# Applied-Procrastination-Fetch-Driver-Cir.net
KiCad netlist of a schematic drawn in EAGLE
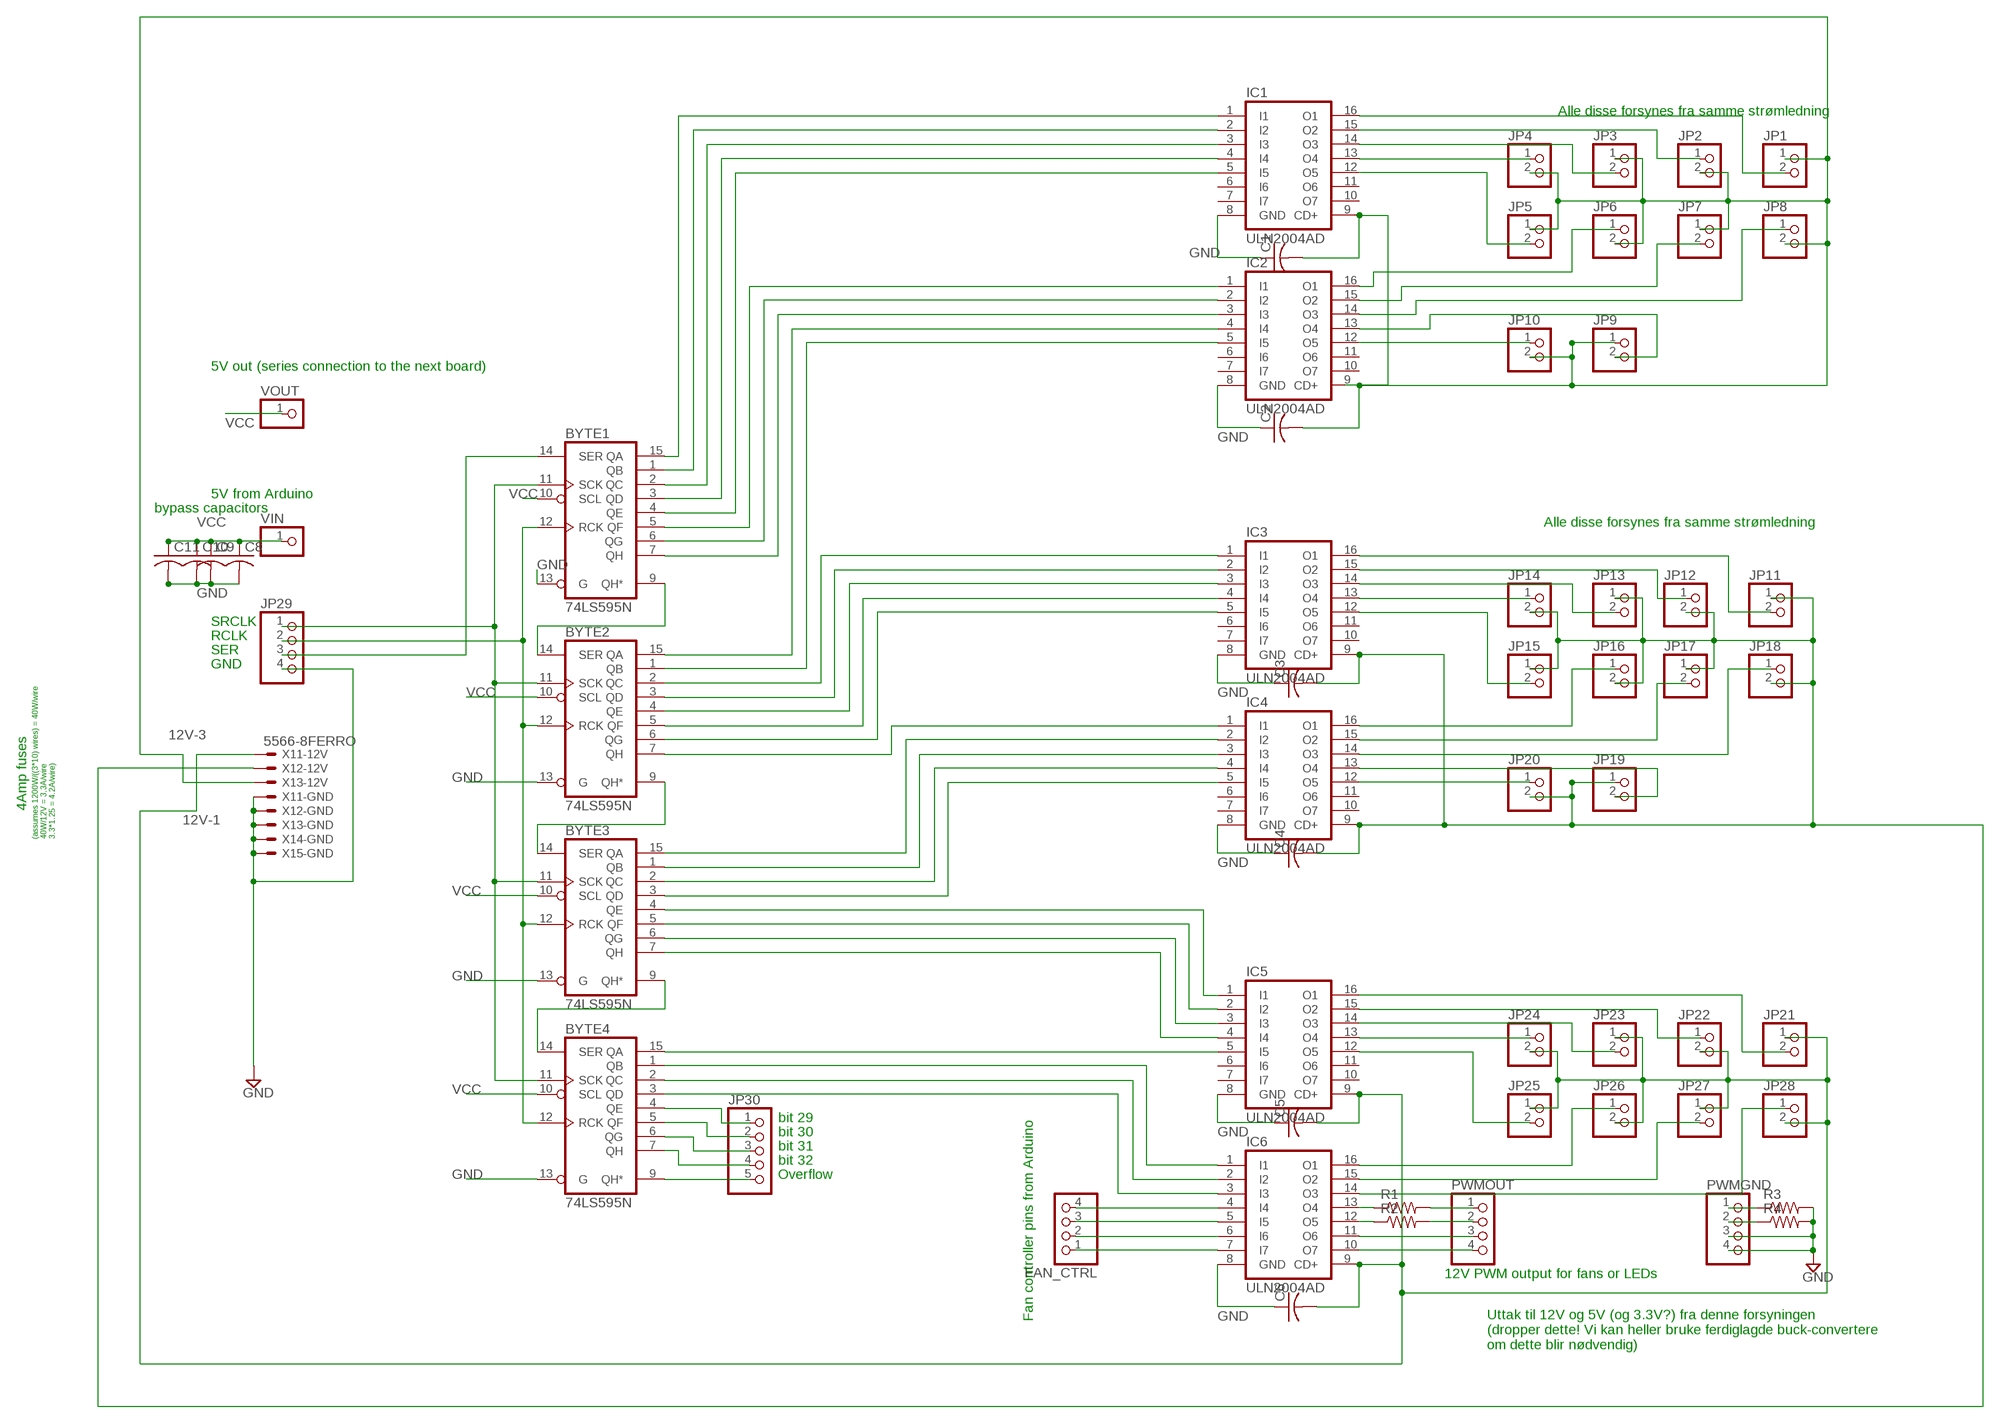
[diagram p0: schematic, sheet 1]

(export (version "E")
  (design (tool "Eeschema 10.0.6"))
  (components
    (comp (ref "BYTE1")
      (value "74LS595N")
      (footprint "eagle-import:DIL16")
      (libsource (lib "eagle-import") (part "74595NLS"))
    )
    (comp (ref "BYTE2")
      (value "74LS595N")
      (footprint "eagle-import:DIL16")
      (libsource (lib "eagle-import") (part "74595NLS"))
    )
    (comp (ref "BYTE3")
      (value "74LS595N")
      (footprint "eagle-import:DIL16")
      (libsource (lib "eagle-import") (part "74595NLS"))
    )
    (comp (ref "BYTE4")
      (value "74LS595N")
      (footprint "eagle-import:DIL16")
      (libsource (lib "eagle-import") (part "74595NLS"))
    )
    (comp (ref "C1")
      (value "C-USC0603")
      (footprint "eagle-import:C0603")
      (libsource (lib "eagle-import") (part "C-USC0603"))
    )
    (comp (ref "C2")
      (value "C-USC0603")
      (footprint "eagle-import:C0603")
      (libsource (lib "eagle-import") (part "C-USC0603"))
    )
    (comp (ref "C3")
      (value "C-USC0603")
      (footprint "eagle-import:C0603")
      (libsource (lib "eagle-import") (part "C-USC0603"))
    )
    (comp (ref "C4")
      (value "C-USC0603")
      (footprint "eagle-import:C0603")
      (libsource (lib "eagle-import") (part "C-USC0603"))
    )
    (comp (ref "C5")
      (value "C-USC0603")
      (footprint "eagle-import:C0603")
      (libsource (lib "eagle-import") (part "C-USC0603"))
    )
    (comp (ref "C6")
      (value "C-USC0603")
      (footprint "eagle-import:C0603")
      (libsource (lib "eagle-import") (part "C-USC0603"))
    )
    (comp (ref "C8")
      (value "C-USC0603")
      (footprint "eagle-import:C0603")
      (libsource (lib "eagle-import") (part "C-USC0603"))
    )
    (comp (ref "C9")
      (value "C-USC0603")
      (footprint "eagle-import:C0603")
      (libsource (lib "eagle-import") (part "C-USC0603"))
    )
    (comp (ref "C10")
      (value "C-USC0603")
      (footprint "eagle-import:C0603")
      (libsource (lib "eagle-import") (part "C-USC0603"))
    )
    (comp (ref "C11")
      (value "C-USC0603")
      (footprint "eagle-import:C0603")
      (libsource (lib "eagle-import") (part "C-USC0603"))
    )
    (comp (ref "FAN_CTRL")
      (value "PINHD-1X4")
      (footprint "eagle-import:1X04")
      (libsource (lib "eagle-import") (part "PINHD-1X4"))
    )
    (comp (ref "IC1")
      (value "ULN2004AD")
      (footprint "eagle-import:SO16")
      (libsource (lib "eagle-import") (part "ULN2004AD"))
    )
    (comp (ref "IC2")
      (value "ULN2004AD")
      (footprint "eagle-import:SO16")
      (libsource (lib "eagle-import") (part "ULN2004AD"))
    )
    (comp (ref "IC3")
      (value "ULN2004AD")
      (footprint "eagle-import:SO16")
      (libsource (lib "eagle-import") (part "ULN2004AD"))
    )
    (comp (ref "IC4")
      (value "ULN2004AD")
      (footprint "eagle-import:SO16")
      (libsource (lib "eagle-import") (part "ULN2004AD"))
    )
    (comp (ref "IC5")
      (value "ULN2004AD")
      (footprint "eagle-import:SO16")
      (libsource (lib "eagle-import") (part "ULN2004AD"))
    )
    (comp (ref "IC6")
      (value "ULN2004AD")
      (footprint "eagle-import:SO16")
      (libsource (lib "eagle-import") (part "ULN2004AD"))
    )
    (comp (ref "JP1")
      (value "PINHD-1X2SOLENOID-R")
      (footprint "eagle-import:SOLENOID-CONTACT-REVERSE")
      (libsource (lib "eagle-import") (part "PINHD-1X2SOLENOID-R"))
    )
    (comp (ref "JP2")
      (value "PINHD-1X2SOLENOID")
      (footprint "eagle-import:SOLENOID-CONTACT")
      (libsource (lib "eagle-import") (part "PINHD-1X2SOLENOID"))
    )
    (comp (ref "JP3")
      (value "PINHD-1X2SOLENOID-R")
      (footprint "eagle-import:SOLENOID-CONTACT-REVERSE")
      (libsource (lib "eagle-import") (part "PINHD-1X2SOLENOID-R"))
    )
    (comp (ref "JP4")
      (value "PINHD-1X2SOLENOID")
      (footprint "eagle-import:SOLENOID-CONTACT")
      (libsource (lib "eagle-import") (part "PINHD-1X2SOLENOID"))
    )
    (comp (ref "JP5")
      (value "PINHD-1X2SOLENOID-R")
      (footprint "eagle-import:SOLENOID-CONTACT-REVERSE")
      (libsource (lib "eagle-import") (part "PINHD-1X2SOLENOID-R"))
    )
    (comp (ref "JP6")
      (value "PINHD-1X2SOLENOID")
      (footprint "eagle-import:SOLENOID-CONTACT")
      (libsource (lib "eagle-import") (part "PINHD-1X2SOLENOID"))
    )
    (comp (ref "JP7")
      (value "PINHD-1X2SOLENOID-R")
      (footprint "eagle-import:SOLENOID-CONTACT-REVERSE")
      (libsource (lib "eagle-import") (part "PINHD-1X2SOLENOID-R"))
    )
    (comp (ref "JP8")
      (value "PINHD-1X2SOLENOID")
      (footprint "eagle-import:SOLENOID-CONTACT")
      (libsource (lib "eagle-import") (part "PINHD-1X2SOLENOID"))
    )
    (comp (ref "JP9")
      (value "PINHD-1X2SOLENOID-R")
      (footprint "eagle-import:SOLENOID-CONTACT-REVERSE")
      (libsource (lib "eagle-import") (part "PINHD-1X2SOLENOID-R"))
    )
    (comp (ref "JP10")
      (value "PINHD-1X2SOLENOID")
      (footprint "eagle-import:SOLENOID-CONTACT")
      (libsource (lib "eagle-import") (part "PINHD-1X2SOLENOID"))
    )
    (comp (ref "JP11")
      (value "PINHD-1X2SOLENOID-R")
      (footprint "eagle-import:SOLENOID-CONTACT-REVERSE")
      (libsource (lib "eagle-import") (part "PINHD-1X2SOLENOID-R"))
    )
    (comp (ref "JP12")
      (value "PINHD-1X2SOLENOID")
      (footprint "eagle-import:SOLENOID-CONTACT")
      (libsource (lib "eagle-import") (part "PINHD-1X2SOLENOID"))
    )
    (comp (ref "JP13")
      (value "PINHD-1X2SOLENOID-R")
      (footprint "eagle-import:SOLENOID-CONTACT-REVERSE")
      (libsource (lib "eagle-import") (part "PINHD-1X2SOLENOID-R"))
    )
    (comp (ref "JP14")
      (value "PINHD-1X2SOLENOID")
      (footprint "eagle-import:SOLENOID-CONTACT")
      (libsource (lib "eagle-import") (part "PINHD-1X2SOLENOID"))
    )
    (comp (ref "JP15")
      (value "PINHD-1X2SOLENOID-R")
      (footprint "eagle-import:SOLENOID-CONTACT-REVERSE")
      (libsource (lib "eagle-import") (part "PINHD-1X2SOLENOID-R"))
    )
    (comp (ref "JP16")
      (value "PINHD-1X2SOLENOID")
      (footprint "eagle-import:SOLENOID-CONTACT")
      (libsource (lib "eagle-import") (part "PINHD-1X2SOLENOID"))
    )
    (comp (ref "JP17")
      (value "PINHD-1X2SOLENOID-R")
      (footprint "eagle-import:SOLENOID-CONTACT-REVERSE")
      (libsource (lib "eagle-import") (part "PINHD-1X2SOLENOID-R"))
    )
    (comp (ref "JP18")
      (value "PINHD-1X2SOLENOID")
      (footprint "eagle-import:SOLENOID-CONTACT")
      (libsource (lib "eagle-import") (part "PINHD-1X2SOLENOID"))
    )
    (comp (ref "JP19")
      (value "PINHD-1X2SOLENOID-R")
      (footprint "eagle-import:SOLENOID-CONTACT-REVERSE")
      (libsource (lib "eagle-import") (part "PINHD-1X2SOLENOID-R"))
    )
    (comp (ref "JP20")
      (value "PINHD-1X2SOLENOID")
      (footprint "eagle-import:SOLENOID-CONTACT")
      (libsource (lib "eagle-import") (part "PINHD-1X2SOLENOID"))
    )
    (comp (ref "JP21")
      (value "PINHD-1X2SOLENOID-R")
      (footprint "eagle-import:SOLENOID-CONTACT-REVERSE")
      (libsource (lib "eagle-import") (part "PINHD-1X2SOLENOID-R"))
    )
    (comp (ref "JP22")
      (value "PINHD-1X2SOLENOID")
      (footprint "eagle-import:SOLENOID-CONTACT")
      (libsource (lib "eagle-import") (part "PINHD-1X2SOLENOID"))
    )
    (comp (ref "JP23")
      (value "PINHD-1X2SOLENOID-R")
      (footprint "eagle-import:SOLENOID-CONTACT-REVERSE")
      (libsource (lib "eagle-import") (part "PINHD-1X2SOLENOID-R"))
    )
    (comp (ref "JP24")
      (value "PINHD-1X2SOLENOID")
      (footprint "eagle-import:SOLENOID-CONTACT")
      (libsource (lib "eagle-import") (part "PINHD-1X2SOLENOID"))
    )
    (comp (ref "JP25")
      (value "PINHD-1X2SOLENOID-R")
      (footprint "eagle-import:SOLENOID-CONTACT-REVERSE")
      (libsource (lib "eagle-import") (part "PINHD-1X2SOLENOID-R"))
    )
    (comp (ref "JP26")
      (value "PINHD-1X2SOLENOID")
      (footprint "eagle-import:SOLENOID-CONTACT")
      (libsource (lib "eagle-import") (part "PINHD-1X2SOLENOID"))
    )
    (comp (ref "JP27")
      (value "PINHD-1X2SOLENOID-R")
      (footprint "eagle-import:SOLENOID-CONTACT-REVERSE")
      (libsource (lib "eagle-import") (part "PINHD-1X2SOLENOID-R"))
    )
    (comp (ref "JP28")
      (value "PINHD-1X2SOLENOID")
      (footprint "eagle-import:SOLENOID-CONTACT")
      (libsource (lib "eagle-import") (part "PINHD-1X2SOLENOID"))
    )
    (comp (ref "JP29")
      (value "PINHD-1X4")
      (footprint "eagle-import:1X04")
      (libsource (lib "eagle-import") (part "PINHD-1X4"))
    )
    (comp (ref "JP30")
      (value "PINHD-1X5")
      (footprint "eagle-import:1X05")
      (libsource (lib "eagle-import") (part "PINHD-1X5"))
    )
    (comp (ref "PWMGND")
      (value "PINHD-1X4")
      (footprint "eagle-import:1X04")
      (libsource (lib "eagle-import") (part "PINHD-1X4"))
    )
    (comp (ref "PWMOUT")
      (value "PINHD-1X4")
      (footprint "eagle-import:1X04")
      (libsource (lib "eagle-import") (part "PINHD-1X4"))
    )
    (comp (ref "R1")
      (value "R-US_R0603")
      (footprint "eagle-import:R0603")
      (libsource (lib "eagle-import") (part "R-US_R0603"))
    )
    (comp (ref "R2")
      (value "R-US_R0603")
      (footprint "eagle-import:R0603")
      (libsource (lib "eagle-import") (part "R-US_R0603"))
    )
    (comp (ref "R3")
      (value "R-US_R0603")
      (footprint "eagle-import:R0603")
      (libsource (lib "eagle-import") (part "R-US_R0603"))
    )
    (comp (ref "R4")
      (value "R-US_R0603")
      (footprint "eagle-import:R0603")
      (libsource (lib "eagle-import") (part "R-US_R0603"))
    )
    (comp (ref "VIN")
      (value "PINHD-1X1")
      (footprint "eagle-import:1X01")
      (libsource (lib "eagle-import") (part "PINHD-1X1"))
    )
    (comp (ref "VOUT")
      (value "PINHD-1X1")
      (footprint "eagle-import:1X01")
      (libsource (lib "eagle-import") (part "PINHD-1X1"))
    )
    (comp (ref "X1")
      (value "5566-8FERRO")
      (footprint "eagle-import:5566-8-CLEAN")
      (libsource (lib "eagle-import") (part "5566-8FERRO"))
    )
  )
  (nets
    (net (code "1") (name "/12V-1") (class "Default")
      (node (ref "C5") (pin "2") (pinfunction "2_2") (pintype "passive"))
      (node (ref "C6") (pin "2") (pinfunction "2_2") (pintype "passive"))
      (node (ref "IC5") (pin "9") (pinfunction "CD+_9") (pintype "passive"))
      (node (ref "IC6") (pin "9") (pinfunction "CD+_9") (pintype "passive"))
      (node (ref "JP21") (pin "1") (pinfunction "1_1") (pintype "passive"))
      (node (ref "JP22") (pin "2") (pinfunction "2_2") (pintype "passive"))
      (node (ref "JP23") (pin "1") (pinfunction "1_1") (pintype "passive"))
      (node (ref "JP24") (pin "2") (pinfunction "2_2") (pintype "passive"))
      (node (ref "JP25") (pin "1") (pinfunction "1_1") (pintype "passive"))
      (node (ref "JP26") (pin "2") (pinfunction "2_2") (pintype "passive"))
      (node (ref "JP27") (pin "1") (pinfunction "1_1") (pintype "passive"))
      (node (ref "JP28") (pin "2") (pinfunction "2_2") (pintype "passive"))
      (node (ref "X1") (pin "1") (pinfunction "S_1") (pintype "passive"))
    )
    (net (code "2") (name "/12V-3") (class "Default")
      (node (ref "C1") (pin "2") (pinfunction "2_2") (pintype "passive"))
      (node (ref "C2") (pin "2") (pinfunction "2_2") (pintype "passive"))
      (node (ref "IC1") (pin "9") (pinfunction "CD+_9") (pintype "passive"))
      (node (ref "IC2") (pin "9") (pinfunction "CD+_9") (pintype "passive"))
      (node (ref "JP1") (pin "1") (pinfunction "1_1") (pintype "passive"))
      (node (ref "JP10") (pin "2") (pinfunction "2_2") (pintype "passive"))
      (node (ref "JP2") (pin "2") (pinfunction "2_2") (pintype "passive"))
      (node (ref "JP3") (pin "1") (pinfunction "1_1") (pintype "passive"))
      (node (ref "JP4") (pin "2") (pinfunction "2_2") (pintype "passive"))
      (node (ref "JP5") (pin "1") (pinfunction "1_1") (pintype "passive"))
      (node (ref "JP6") (pin "2") (pinfunction "2_2") (pintype "passive"))
      (node (ref "JP7") (pin "1") (pinfunction "1_1") (pintype "passive"))
      (node (ref "JP8") (pin "2") (pinfunction "2_2") (pintype "passive"))
      (node (ref "JP9") (pin "1") (pinfunction "1_1") (pintype "passive"))
      (node (ref "X1") (pin "3") (pinfunction "S_3") (pintype "passive"))
    )
    (net (code "3") (name "/VCC") (class "Default")
      (node (ref "BYTE1") (pin "10") (pinfunction "SCL_10") (pintype "input"))
      (node (ref "BYTE2") (pin "10") (pinfunction "SCL_10") (pintype "input"))
      (node (ref "BYTE3") (pin "10") (pinfunction "SCL_10") (pintype "input"))
      (node (ref "BYTE4") (pin "10") (pinfunction "SCL_10") (pintype "input"))
      (node (ref "C10") (pin "1") (pinfunction "1_1") (pintype "passive"))
      (node (ref "C11") (pin "1") (pinfunction "1_1") (pintype "passive"))
      (node (ref "C8") (pin "1") (pinfunction "1_1") (pintype "passive"))
      (node (ref "C9") (pin "1") (pinfunction "1_1") (pintype "passive"))
      (node (ref "VIN") (pin "1") (pinfunction "1_1") (pintype "passive"))
      (node (ref "VOUT") (pin "1") (pinfunction "1_1") (pintype "passive"))
    )
    (net (code "4") (name "GND") (class "Default")
      (node (ref "BYTE1") (pin "13") (pinfunction "G_13") (pintype "input"))
      (node (ref "BYTE2") (pin "13") (pinfunction "G_13") (pintype "input"))
      (node (ref "BYTE3") (pin "13") (pinfunction "G_13") (pintype "input"))
      (node (ref "BYTE4") (pin "13") (pinfunction "G_13") (pintype "input"))
      (node (ref "C1") (pin "1") (pinfunction "1_1") (pintype "passive"))
      (node (ref "C10") (pin "2") (pinfunction "2_2") (pintype "passive"))
      (node (ref "C11") (pin "2") (pinfunction "2_2") (pintype "passive"))
      (node (ref "C2") (pin "1") (pinfunction "1_1") (pintype "passive"))
      (node (ref "C3") (pin "1") (pinfunction "1_1") (pintype "passive"))
      (node (ref "C4") (pin "1") (pinfunction "1_1") (pintype "passive"))
      (node (ref "C5") (pin "1") (pinfunction "1_1") (pintype "passive"))
      (node (ref "C6") (pin "1") (pinfunction "1_1") (pintype "passive"))
      (node (ref "C8") (pin "2") (pinfunction "2_2") (pintype "passive"))
      (node (ref "C9") (pin "2") (pinfunction "2_2") (pintype "passive"))
      (node (ref "IC1") (pin "8") (pinfunction "GND_8") (pintype "power_in"))
      (node (ref "IC2") (pin "8") (pinfunction "GND_8") (pintype "power_in"))
      (node (ref "IC3") (pin "8") (pinfunction "GND_8") (pintype "power_in"))
      (node (ref "IC4") (pin "8") (pinfunction "GND_8") (pintype "power_in"))
      (node (ref "IC5") (pin "8") (pinfunction "GND_8") (pintype "power_in"))
      (node (ref "IC6") (pin "8") (pinfunction "GND_8") (pintype "power_in"))
      (node (ref "JP29") (pin "4") (pinfunction "4_4") (pintype "passive"))
      (node (ref "PWMGND") (pin "3") (pinfunction "3_3") (pintype "passive"))
      (node (ref "PWMGND") (pin "4") (pinfunction "4_4") (pintype "passive"))
      (node (ref "R3") (pin "2") (pinfunction "2_2") (pintype "passive"))
      (node (ref "R4") (pin "2") (pinfunction "2_2") (pintype "passive"))
      (node (ref "X1") (pin "4") (pinfunction "S_4") (pintype "passive"))
      (node (ref "X1") (pin "5") (pinfunction "S_5") (pintype "passive"))
      (node (ref "X1") (pin "6") (pinfunction "S_6") (pintype "passive"))
      (node (ref "X1") (pin "7") (pinfunction "S_7") (pintype "passive"))
      (node (ref "X1") (pin "8") (pinfunction "S_8") (pintype "passive"))
    )
    (net (code "5") (name "Net-(BYTE1A-QA)") (class "Default")
      (node (ref "BYTE1") (pin "15") (pinfunction "QA_15") (pintype "tri_state"))
      (node (ref "IC1") (pin "1") (pinfunction "I1_1") (pintype "input"))
    )
    (net (code "6") (name "Net-(BYTE1A-QB)") (class "Default")
      (node (ref "BYTE1") (pin "1") (pinfunction "QB_1") (pintype "tri_state"))
      (node (ref "IC1") (pin "2") (pinfunction "I2_2") (pintype "input"))
    )
    (net (code "7") (name "Net-(BYTE1A-QC)") (class "Default")
      (node (ref "BYTE1") (pin "2") (pinfunction "QC_2") (pintype "tri_state"))
      (node (ref "IC1") (pin "3") (pinfunction "I3_3") (pintype "input"))
    )
    (net (code "8") (name "Net-(BYTE1A-QD)") (class "Default")
      (node (ref "BYTE1") (pin "3") (pinfunction "QD_3") (pintype "tri_state"))
      (node (ref "IC1") (pin "4") (pinfunction "I4_4") (pintype "input"))
    )
    (net (code "9") (name "Net-(BYTE1A-QE)") (class "Default")
      (node (ref "BYTE1") (pin "4") (pinfunction "QE_4") (pintype "tri_state"))
      (node (ref "IC1") (pin "5") (pinfunction "I5_5") (pintype "input"))
    )
    (net (code "10") (name "Net-(BYTE1A-QF)") (class "Default")
      (node (ref "BYTE1") (pin "5") (pinfunction "QF_5") (pintype "tri_state"))
      (node (ref "IC2") (pin "1") (pinfunction "I1_1") (pintype "input"))
    )
    (net (code "11") (name "Net-(BYTE1A-QG)") (class "Default")
      (node (ref "BYTE1") (pin "6") (pinfunction "QG_6") (pintype "tri_state"))
      (node (ref "IC2") (pin "2") (pinfunction "I2_2") (pintype "input"))
    )
    (net (code "12") (name "Net-(BYTE1A-QH)") (class "Default")
      (node (ref "BYTE1") (pin "7") (pinfunction "QH_7") (pintype "tri_state"))
      (node (ref "IC2") (pin "3") (pinfunction "I3_3") (pintype "input"))
    )
    (net (code "13") (name "Net-(BYTE1A-QH*)") (class "Default")
      (node (ref "BYTE1") (pin "9") (pinfunction "QH*_9") (pintype "tri_state"))
      (node (ref "BYTE2") (pin "14") (pinfunction "SER_14") (pintype "input"))
    )
    (net (code "14") (name "Net-(BYTE1A-RCK)") (class "Default")
      (node (ref "BYTE1") (pin "12") (pinfunction "RCK_12") (pintype "input"))
      (node (ref "BYTE2") (pin "12") (pinfunction "RCK_12") (pintype "input"))
      (node (ref "BYTE3") (pin "12") (pinfunction "RCK_12") (pintype "input"))
      (node (ref "BYTE4") (pin "12") (pinfunction "RCK_12") (pintype "input"))
      (node (ref "JP29") (pin "2") (pinfunction "2_2") (pintype "passive"))
    )
    (net (code "15") (name "Net-(BYTE1A-SCK)") (class "Default")
      (node (ref "BYTE1") (pin "11") (pinfunction "SCK_11") (pintype "input"))
      (node (ref "BYTE2") (pin "11") (pinfunction "SCK_11") (pintype "input"))
      (node (ref "BYTE3") (pin "11") (pinfunction "SCK_11") (pintype "input"))
      (node (ref "BYTE4") (pin "11") (pinfunction "SCK_11") (pintype "input"))
      (node (ref "JP29") (pin "1") (pinfunction "1_1") (pintype "passive"))
    )
    (net (code "16") (name "Net-(BYTE1A-SER)") (class "Default")
      (node (ref "BYTE1") (pin "14") (pinfunction "SER_14") (pintype "input"))
      (node (ref "JP29") (pin "3") (pinfunction "3_3") (pintype "passive"))
    )
    (net (code "17") (name "Net-(BYTE2A-QA)") (class "Default")
      (node (ref "BYTE2") (pin "15") (pinfunction "QA_15") (pintype "tri_state"))
      (node (ref "IC2") (pin "4") (pinfunction "I4_4") (pintype "input"))
    )
    (net (code "18") (name "Net-(BYTE2A-QB)") (class "Default")
      (node (ref "BYTE2") (pin "1") (pinfunction "QB_1") (pintype "tri_state"))
      (node (ref "IC2") (pin "5") (pinfunction "I5_5") (pintype "input"))
    )
    (net (code "19") (name "Net-(BYTE2A-QC)") (class "Default")
      (node (ref "BYTE2") (pin "2") (pinfunction "QC_2") (pintype "tri_state"))
      (node (ref "IC3") (pin "1") (pinfunction "I1_1") (pintype "input"))
    )
    (net (code "20") (name "Net-(BYTE2A-QD)") (class "Default")
      (node (ref "BYTE2") (pin "3") (pinfunction "QD_3") (pintype "tri_state"))
      (node (ref "IC3") (pin "2") (pinfunction "I2_2") (pintype "input"))
    )
    (net (code "21") (name "Net-(BYTE2A-QE)") (class "Default")
      (node (ref "BYTE2") (pin "4") (pinfunction "QE_4") (pintype "tri_state"))
      (node (ref "IC3") (pin "3") (pinfunction "I3_3") (pintype "input"))
    )
    (net (code "22") (name "Net-(BYTE2A-QF)") (class "Default")
      (node (ref "BYTE2") (pin "5") (pinfunction "QF_5") (pintype "tri_state"))
      (node (ref "IC3") (pin "4") (pinfunction "I4_4") (pintype "input"))
    )
    (net (code "23") (name "Net-(BYTE2A-QG)") (class "Default")
      (node (ref "BYTE2") (pin "6") (pinfunction "QG_6") (pintype "tri_state"))
      (node (ref "IC3") (pin "5") (pinfunction "I5_5") (pintype "input"))
    )
    (net (code "24") (name "Net-(BYTE2A-QH)") (class "Default")
      (node (ref "BYTE2") (pin "7") (pinfunction "QH_7") (pintype "tri_state"))
      (node (ref "IC4") (pin "1") (pinfunction "I1_1") (pintype "input"))
    )
    (net (code "25") (name "Net-(BYTE2A-QH*)") (class "Default")
      (node (ref "BYTE2") (pin "9") (pinfunction "QH*_9") (pintype "tri_state"))
      (node (ref "BYTE3") (pin "14") (pinfunction "SER_14") (pintype "input"))
    )
    (net (code "26") (name "Net-(BYTE3A-QA)") (class "Default")
      (node (ref "BYTE3") (pin "15") (pinfunction "QA_15") (pintype "tri_state"))
      (node (ref "IC4") (pin "2") (pinfunction "I2_2") (pintype "input"))
    )
    (net (code "27") (name "Net-(BYTE3A-QB)") (class "Default")
      (node (ref "BYTE3") (pin "1") (pinfunction "QB_1") (pintype "tri_state"))
      (node (ref "IC4") (pin "3") (pinfunction "I3_3") (pintype "input"))
    )
    (net (code "28") (name "Net-(BYTE3A-QC)") (class "Default")
      (node (ref "BYTE3") (pin "2") (pinfunction "QC_2") (pintype "tri_state"))
      (node (ref "IC4") (pin "4") (pinfunction "I4_4") (pintype "input"))
    )
    (net (code "29") (name "Net-(BYTE3A-QD)") (class "Default")
      (node (ref "BYTE3") (pin "3") (pinfunction "QD_3") (pintype "tri_state"))
      (node (ref "IC4") (pin "5") (pinfunction "I5_5") (pintype "input"))
    )
    (net (code "30") (name "Net-(BYTE3A-QE)") (class "Default")
      (node (ref "BYTE3") (pin "4") (pinfunction "QE_4") (pintype "tri_state"))
      (node (ref "IC5") (pin "1") (pinfunction "I1_1") (pintype "input"))
    )
    (net (code "31") (name "Net-(BYTE3A-QF)") (class "Default")
      (node (ref "BYTE3") (pin "5") (pinfunction "QF_5") (pintype "tri_state"))
      (node (ref "IC5") (pin "2") (pinfunction "I2_2") (pintype "input"))
    )
    (net (code "32") (name "Net-(BYTE3A-QG)") (class "Default")
      (node (ref "BYTE3") (pin "6") (pinfunction "QG_6") (pintype "tri_state"))
      (node (ref "IC5") (pin "3") (pinfunction "I3_3") (pintype "input"))
    )
    (net (code "33") (name "Net-(BYTE3A-QH)") (class "Default")
      (node (ref "BYTE3") (pin "7") (pinfunction "QH_7") (pintype "tri_state"))
      (node (ref "IC5") (pin "4") (pinfunction "I4_4") (pintype "input"))
    )
    (net (code "34") (name "Net-(BYTE3A-QH*)") (class "Default")
      (node (ref "BYTE3") (pin "9") (pinfunction "QH*_9") (pintype "tri_state"))
      (node (ref "BYTE4") (pin "14") (pinfunction "SER_14") (pintype "input"))
    )
    (net (code "35") (name "Net-(BYTE4A-QA)") (class "Default")
      (node (ref "BYTE4") (pin "15") (pinfunction "QA_15") (pintype "tri_state"))
      (node (ref "IC5") (pin "5") (pinfunction "I5_5") (pintype "input"))
    )
    (net (code "36") (name "Net-(BYTE4A-QB)") (class "Default")
      (node (ref "BYTE4") (pin "1") (pinfunction "QB_1") (pintype "tri_state"))
      (node (ref "IC6") (pin "1") (pinfunction "I1_1") (pintype "input"))
    )
    (net (code "37") (name "Net-(BYTE4A-QC)") (class "Default")
      (node (ref "BYTE4") (pin "2") (pinfunction "QC_2") (pintype "tri_state"))
      (node (ref "IC6") (pin "2") (pinfunction "I2_2") (pintype "input"))
    )
    (net (code "38") (name "Net-(BYTE4A-QD)") (class "Default")
      (node (ref "BYTE4") (pin "3") (pinfunction "QD_3") (pintype "tri_state"))
      (node (ref "IC6") (pin "3") (pinfunction "I3_3") (pintype "input"))
    )
    (net (code "39") (name "Net-(BYTE4A-QE)") (class "Default")
      (node (ref "BYTE4") (pin "4") (pinfunction "QE_4") (pintype "tri_state"))
      (node (ref "JP30") (pin "1") (pinfunction "1_1") (pintype "passive"))
    )
    (net (code "40") (name "Net-(BYTE4A-QF)") (class "Default")
      (node (ref "BYTE4") (pin "5") (pinfunction "QF_5") (pintype "tri_state"))
      (node (ref "JP30") (pin "2") (pinfunction "2_2") (pintype "passive"))
    )
    (net (code "41") (name "Net-(BYTE4A-QG)") (class "Default")
      (node (ref "BYTE4") (pin "6") (pinfunction "QG_6") (pintype "tri_state"))
      (node (ref "JP30") (pin "3") (pinfunction "3_3") (pintype "passive"))
    )
    (net (code "42") (name "Net-(BYTE4A-QH)") (class "Default")
      (node (ref "BYTE4") (pin "7") (pinfunction "QH_7") (pintype "tri_state"))
      (node (ref "JP30") (pin "4") (pinfunction "4_4") (pintype "passive"))
    )
    (net (code "43") (name "Net-(BYTE4A-QH*)") (class "Default")
      (node (ref "BYTE4") (pin "9") (pinfunction "QH*_9") (pintype "tri_state"))
      (node (ref "JP30") (pin "5") (pinfunction "5_5") (pintype "passive"))
    )
    (net (code "44") (name "Net-(IC1-O1)") (class "Default")
      (node (ref "IC1") (pin "16") (pinfunction "O1_16") (pintype "open_collector"))
      (node (ref "JP1") (pin "2") (pinfunction "2_2") (pintype "passive"))
    )
    (net (code "45") (name "Net-(IC1-O2)") (class "Default")
      (node (ref "IC1") (pin "15") (pinfunction "O2_15") (pintype "open_collector"))
      (node (ref "JP2") (pin "1") (pinfunction "1_1") (pintype "passive"))
    )
    (net (code "46") (name "Net-(IC1-O3)") (class "Default")
      (node (ref "IC1") (pin "14") (pinfunction "O3_14") (pintype "open_collector"))
      (node (ref "JP3") (pin "2") (pinfunction "2_2") (pintype "passive"))
    )
    (net (code "47") (name "Net-(IC1-O4)") (class "Default")
      (node (ref "IC1") (pin "13") (pinfunction "O4_13") (pintype "open_collector"))
      (node (ref "JP4") (pin "1") (pinfunction "1_1") (pintype "passive"))
    )
    (net (code "48") (name "Net-(IC1-O5)") (class "Default")
      (node (ref "IC1") (pin "12") (pinfunction "O5_12") (pintype "open_collector"))
      (node (ref "JP5") (pin "2") (pinfunction "2_2") (pintype "passive"))
    )
    (net (code "49") (name "Net-(IC2-O1)") (class "Default")
      (node (ref "IC2") (pin "16") (pinfunction "O1_16") (pintype "open_collector"))
      (node (ref "JP6") (pin "1") (pinfunction "1_1") (pintype "passive"))
    )
    (net (code "50") (name "Net-(IC2-O2)") (class "Default")
      (node (ref "IC2") (pin "15") (pinfunction "O2_15") (pintype "open_collector"))
      (node (ref "JP7") (pin "2") (pinfunction "2_2") (pintype "passive"))
    )
    (net (code "51") (name "Net-(IC2-O3)") (class "Default")
      (node (ref "IC2") (pin "14") (pinfunction "O3_14") (pintype "open_collector"))
      (node (ref "JP8") (pin "1") (pinfunction "1_1") (pintype "passive"))
    )
    (net (code "52") (name "Net-(IC2-O4)") (class "Default")
      (node (ref "IC2") (pin "13") (pinfunction "O4_13") (pintype "open_collector"))
      (node (ref "JP9") (pin "2") (pinfunction "2_2") (pintype "passive"))
    )
    (net (code "53") (name "Net-(IC2-O5)") (class "Default")
      (node (ref "IC2") (pin "12") (pinfunction "O5_12") (pintype "open_collector"))
      (node (ref "JP10") (pin "1") (pinfunction "1_1") (pintype "passive"))
    )
    (net (code "54") (name "Net-(IC3-CD+)") (class "Default")
      (node (ref "C3") (pin "2") (pinfunction "2_2") (pintype "passive"))
      (node (ref "C4") (pin "2") (pinfunction "2_2") (pintype "passive"))
      (node (ref "IC3") (pin "9") (pinfunction "CD+_9") (pintype "passive"))
      (node (ref "IC4") (pin "9") (pinfunction "CD+_9") (pintype "passive"))
      (node (ref "JP11") (pin "1") (pinfunction "1_1") (pintype "passive"))
      (node (ref "JP12") (pin "2") (pinfunction "2_2") (pintype "passive"))
      (node (ref "JP13") (pin "1") (pinfunction "1_1") (pintype "passive"))
      (node (ref "JP14") (pin "2") (pinfunction "2_2") (pintype "passive"))
      (node (ref "JP15") (pin "1") (pinfunction "1_1") (pintype "passive"))
      (node (ref "JP16") (pin "2") (pinfunction "2_2") (pintype "passive"))
      (node (ref "JP17") (pin "1") (pinfunction "1_1") (pintype "passive"))
      (node (ref "JP18") (pin "2") (pinfunction "2_2") (pintype "passive"))
      (node (ref "JP19") (pin "1") (pinfunction "1_1") (pintype "passive"))
      (node (ref "JP20") (pin "2") (pinfunction "2_2") (pintype "passive"))
      (node (ref "X1") (pin "2") (pinfunction "S_2") (pintype "passive"))
    )
    (net (code "55") (name "Net-(IC3-O1)") (class "Default")
      (node (ref "IC3") (pin "16") (pinfunction "O1_16") (pintype "open_collector"))
      (node (ref "JP11") (pin "2") (pinfunction "2_2") (pintype "passive"))
    )
    (net (code "56") (name "Net-(IC3-O2)") (class "Default")
      (node (ref "IC3") (pin "15") (pinfunction "O2_15") (pintype "open_collector"))
      (node (ref "JP12") (pin "1") (pinfunction "1_1") (pintype "passive"))
    )
    (net (code "57") (name "Net-(IC3-O3)") (class "Default")
      (node (ref "IC3") (pin "14") (pinfunction "O3_14") (pintype "open_collector"))
      (node (ref "JP13") (pin "2") (pinfunction "2_2") (pintype "passive"))
    )
    (net (code "58") (name "Net-(IC3-O4)") (class "Default")
      (node (ref "IC3") (pin "13") (pinfunction "O4_13") (pintype "open_collector"))
      (node (ref "JP14") (pin "1") (pinfunction "1_1") (pintype "passive"))
    )
    (net (code "59") (name "Net-(IC3-O5)") (class "Default")
      (node (ref "IC3") (pin "12") (pinfunction "O5_12") (pintype "open_collector"))
      (node (ref "JP15") (pin "2") (pinfunction "2_2") (pintype "passive"))
    )
    (net (code "60") (name "Net-(IC4-O1)") (class "Default")
      (node (ref "IC4") (pin "16") (pinfunction "O1_16") (pintype "open_collector"))
      (node (ref "JP16") (pin "1") (pinfunction "1_1") (pintype "passive"))
    )
    (net (code "61") (name "Net-(IC4-O2)") (class "Default")
      (node (ref "IC4") (pin "15") (pinfunction "O2_15") (pintype "open_collector"))
      (node (ref "JP17") (pin "2") (pinfunction "2_2") (pintype "passive"))
    )
    (net (code "62") (name "Net-(IC4-O3)") (class "Default")
      (node (ref "IC4") (pin "14") (pinfunction "O3_14") (pintype "open_collector"))
      (node (ref "JP18") (pin "1") (pinfunction "1_1") (pintype "passive"))
    )
    (net (code "63") (name "Net-(IC4-O4)") (class "Default")
      (node (ref "IC4") (pin "13") (pinfunction "O4_13") (pintype "open_collector"))
      (node (ref "JP19") (pin "2") (pinfunction "2_2") (pintype "passive"))
    )
    (net (code "64") (name "Net-(IC4-O5)") (class "Default")
      (node (ref "IC4") (pin "12") (pinfunction "O5_12") (pintype "open_collector"))
      (node (ref "JP20") (pin "1") (pinfunction "1_1") (pintype "passive"))
    )
    (net (code "65") (name "Net-(IC5-O1)") (class "Default")
      (node (ref "IC5") (pin "16") (pinfunction "O1_16") (pintype "open_collector"))
      (node (ref "JP21") (pin "2") (pinfunction "2_2") (pintype "passive"))
    )
    (net (code "66") (name "Net-(IC5-O2)") (class "Default")
      (node (ref "IC5") (pin "15") (pinfunction "O2_15") (pintype "open_collector"))
      (node (ref "JP22") (pin "1") (pinfunction "1_1") (pintype "passive"))
    )
    (net (code "67") (name "Net-(IC5-O3)") (class "Default")
      (node (ref "IC5") (pin "14") (pinfunction "O3_14") (pintype "open_collector"))
      (node (ref "JP23") (pin "2") (pinfunction "2_2") (pintype "passive"))
    )
    (net (code "68") (name "Net-(IC5-O4)") (class "Default")
      (node (ref "IC5") (pin "13") (pinfunction "O4_13") (pintype "open_collector"))
      (node (ref "JP24") (pin "1") (pinfunction "1_1") (pintype "passive"))
    )
    (net (code "69") (name "Net-(IC5-O5)") (class "Default")
      (node (ref "IC5") (pin "12") (pinfunction "O5_12") (pintype "open_collector"))
      (node (ref "JP25") (pin "2") (pinfunction "2_2") (pintype "passive"))
    )
    (net (code "70") (name "Net-(IC6-I4)") (class "Default")
      (node (ref "FAN_CTRL") (pin "4") (pinfunction "4_4") (pintype "passive"))
      (node (ref "IC6") (pin "4") (pinfunction "I4_4") (pintype "input"))
    )
    (net (code "71") (name "Net-(IC6-I5)") (class "Default")
      (node (ref "FAN_CTRL") (pin "3") (pinfunction "3_3") (pintype "passive"))
      (node (ref "IC6") (pin "5") (pinfunction "I5_5") (pintype "input"))
    )
    (net (code "72") (name "Net-(IC6-I6)") (class "Default")
      (node (ref "FAN_CTRL") (pin "2") (pinfunction "2_2") (pintype "passive"))
      (node (ref "IC6") (pin "6") (pinfunction "I6_6") (pintype "input"))
    )
    (net (code "73") (name "Net-(IC6-I7)") (class "Default")
      (node (ref "FAN_CTRL") (pin "1") (pinfunction "1_1") (pintype "passive"))
      (node (ref "IC6") (pin "7") (pinfunction "I7_7") (pintype "input"))
    )
    (net (code "74") (name "Net-(IC6-O1)") (class "Default")
      (node (ref "IC6") (pin "16") (pinfunction "O1_16") (pintype "open_collector"))
      (node (ref "JP26") (pin "1") (pinfunction "1_1") (pintype "passive"))
    )
    (net (code "75") (name "Net-(IC6-O2)") (class "Default")
      (node (ref "IC6") (pin "15") (pinfunction "O2_15") (pintype "open_collector"))
      (node (ref "JP27") (pin "2") (pinfunction "2_2") (pintype "passive"))
    )
    (net (code "76") (name "Net-(IC6-O3)") (class "Default")
      (node (ref "IC6") (pin "14") (pinfunction "O3_14") (pintype "open_collector"))
      (node (ref "JP28") (pin "1") (pinfunction "1_1") (pintype "passive"))
    )
    (net (code "77") (name "Net-(IC6-O4)") (class "Default")
      (node (ref "IC6") (pin "13") (pinfunction "O4_13") (pintype "open_collector"))
      (node (ref "R1") (pin "1") (pinfunction "1_1") (pintype "passive"))
    )
    (net (code "78") (name "Net-(IC6-O5)") (class "Default")
      (node (ref "IC6") (pin "12") (pinfunction "O5_12") (pintype "open_collector"))
      (node (ref "R2") (pin "1") (pinfunction "1_1") (pintype "passive"))
    )
    (net (code "79") (name "Net-(IC6-O6)") (class "Default")
      (node (ref "IC6") (pin "11") (pinfunction "O6_11") (pintype "open_collector"))
      (node (ref "PWMOUT") (pin "3") (pinfunction "3_3") (pintype "passive"))
    )
    (net (code "80") (name "Net-(IC6-O7)") (class "Default")
      (node (ref "IC6") (pin "10") (pinfunction "O7_10") (pintype "open_collector"))
      (node (ref "PWMOUT") (pin "4") (pinfunction "4_4") (pintype "passive"))
    )
    (net (code "81") (name "Net-(PWMGND-Pad1)") (class "Default")
      (node (ref "PWMGND") (pin "1") (pinfunction "1_1") (pintype "passive"))
      (node (ref "R3") (pin "1") (pinfunction "1_1") (pintype "passive"))
    )
    (net (code "82") (name "Net-(PWMGND-Pad2)") (class "Default")
      (node (ref "PWMGND") (pin "2") (pinfunction "2_2") (pintype "passive"))
      (node (ref "R4") (pin "1") (pinfunction "1_1") (pintype "passive"))
    )
    (net (code "83") (name "Net-(PWMOUT-Pad1)") (class "Default")
      (node (ref "PWMOUT") (pin "1") (pinfunction "1_1") (pintype "passive"))
      (node (ref "R1") (pin "2") (pinfunction "2_2") (pintype "passive"))
    )
    (net (code "84") (name "Net-(PWMOUT-Pad2)") (class "Default")
      (node (ref "PWMOUT") (pin "2") (pinfunction "2_2") (pintype "passive"))
      (node (ref "R2") (pin "2") (pinfunction "2_2") (pintype "passive"))
    )
    (net (code "85") (name "unconnected-(IC1-I6-Pad6)") (class "Default")
      (node (ref "IC1") (pin "6") (pinfunction "I6_6") (pintype "input"))
    )
    (net (code "86") (name "unconnected-(IC1-I7-Pad7)") (class "Default")
      (node (ref "IC1") (pin "7") (pinfunction "I7_7") (pintype "input"))
    )
    (net (code "87") (name "unconnected-(IC1-O6-Pad11)") (class "Default")
      (node (ref "IC1") (pin "11") (pinfunction "O6_11") (pintype "open_collector"))
    )
    (net (code "88") (name "unconnected-(IC1-O7-Pad10)") (class "Default")
      (node (ref "IC1") (pin "10") (pinfunction "O7_10") (pintype "open_collector"))
    )
    (net (code "89") (name "unconnected-(IC2-I6-Pad6)") (class "Default")
      (node (ref "IC2") (pin "6") (pinfunction "I6_6") (pintype "input"))
    )
    (net (code "90") (name "unconnected-(IC2-I7-Pad7)") (class "Default")
      (node (ref "IC2") (pin "7") (pinfunction "I7_7") (pintype "input"))
    )
    (net (code "91") (name "unconnected-(IC2-O6-Pad11)") (class "Default")
      (node (ref "IC2") (pin "11") (pinfunction "O6_11") (pintype "open_collector"))
    )
    (net (code "92") (name "unconnected-(IC2-O7-Pad10)") (class "Default")
      (node (ref "IC2") (pin "10") (pinfunction "O7_10") (pintype "open_collector"))
    )
    (net (code "93") (name "unconnected-(IC3-I6-Pad6)") (class "Default")
      (node (ref "IC3") (pin "6") (pinfunction "I6_6") (pintype "input"))
    )
    (net (code "94") (name "unconnected-(IC3-I7-Pad7)") (class "Default")
      (node (ref "IC3") (pin "7") (pinfunction "I7_7") (pintype "input"))
    )
    (net (code "95") (name "unconnected-(IC3-O6-Pad11)") (class "Default")
      (node (ref "IC3") (pin "11") (pinfunction "O6_11") (pintype "open_collector"))
    )
    (net (code "96") (name "unconnected-(IC3-O7-Pad10)") (class "Default")
      (node (ref "IC3") (pin "10") (pinfunction "O7_10") (pintype "open_collector"))
    )
    (net (code "97") (name "unconnected-(IC4-I6-Pad6)") (class "Default")
      (node (ref "IC4") (pin "6") (pinfunction "I6_6") (pintype "input"))
    )
    (net (code "98") (name "unconnected-(IC4-I7-Pad7)") (class "Default")
      (node (ref "IC4") (pin "7") (pinfunction "I7_7") (pintype "input"))
    )
    (net (code "99") (name "unconnected-(IC4-O6-Pad11)") (class "Default")
      (node (ref "IC4") (pin "11") (pinfunction "O6_11") (pintype "open_collector"))
    )
    (net (code "100") (name "unconnected-(IC4-O7-Pad10)") (class "Default")
      (node (ref "IC4") (pin "10") (pinfunction "O7_10") (pintype "open_collector"))
    )
    (net (code "101") (name "unconnected-(IC5-I6-Pad6)") (class "Default")
      (node (ref "IC5") (pin "6") (pinfunction "I6_6") (pintype "input"))
    )
    (net (code "102") (name "unconnected-(IC5-I7-Pad7)") (class "Default")
      (node (ref "IC5") (pin "7") (pinfunction "I7_7") (pintype "input"))
    )
    (net (code "103") (name "unconnected-(IC5-O6-Pad11)") (class "Default")
      (node (ref "IC5") (pin "11") (pinfunction "O6_11") (pintype "open_collector"))
    )
    (net (code "104") (name "unconnected-(IC5-O7-Pad10)") (class "Default")
      (node (ref "IC5") (pin "10") (pinfunction "O7_10") (pintype "open_collector"))
    )
  )
)
